# 608_AICarBoard_030102.net
KiCad netlist of a schematic drawn in EAGLE
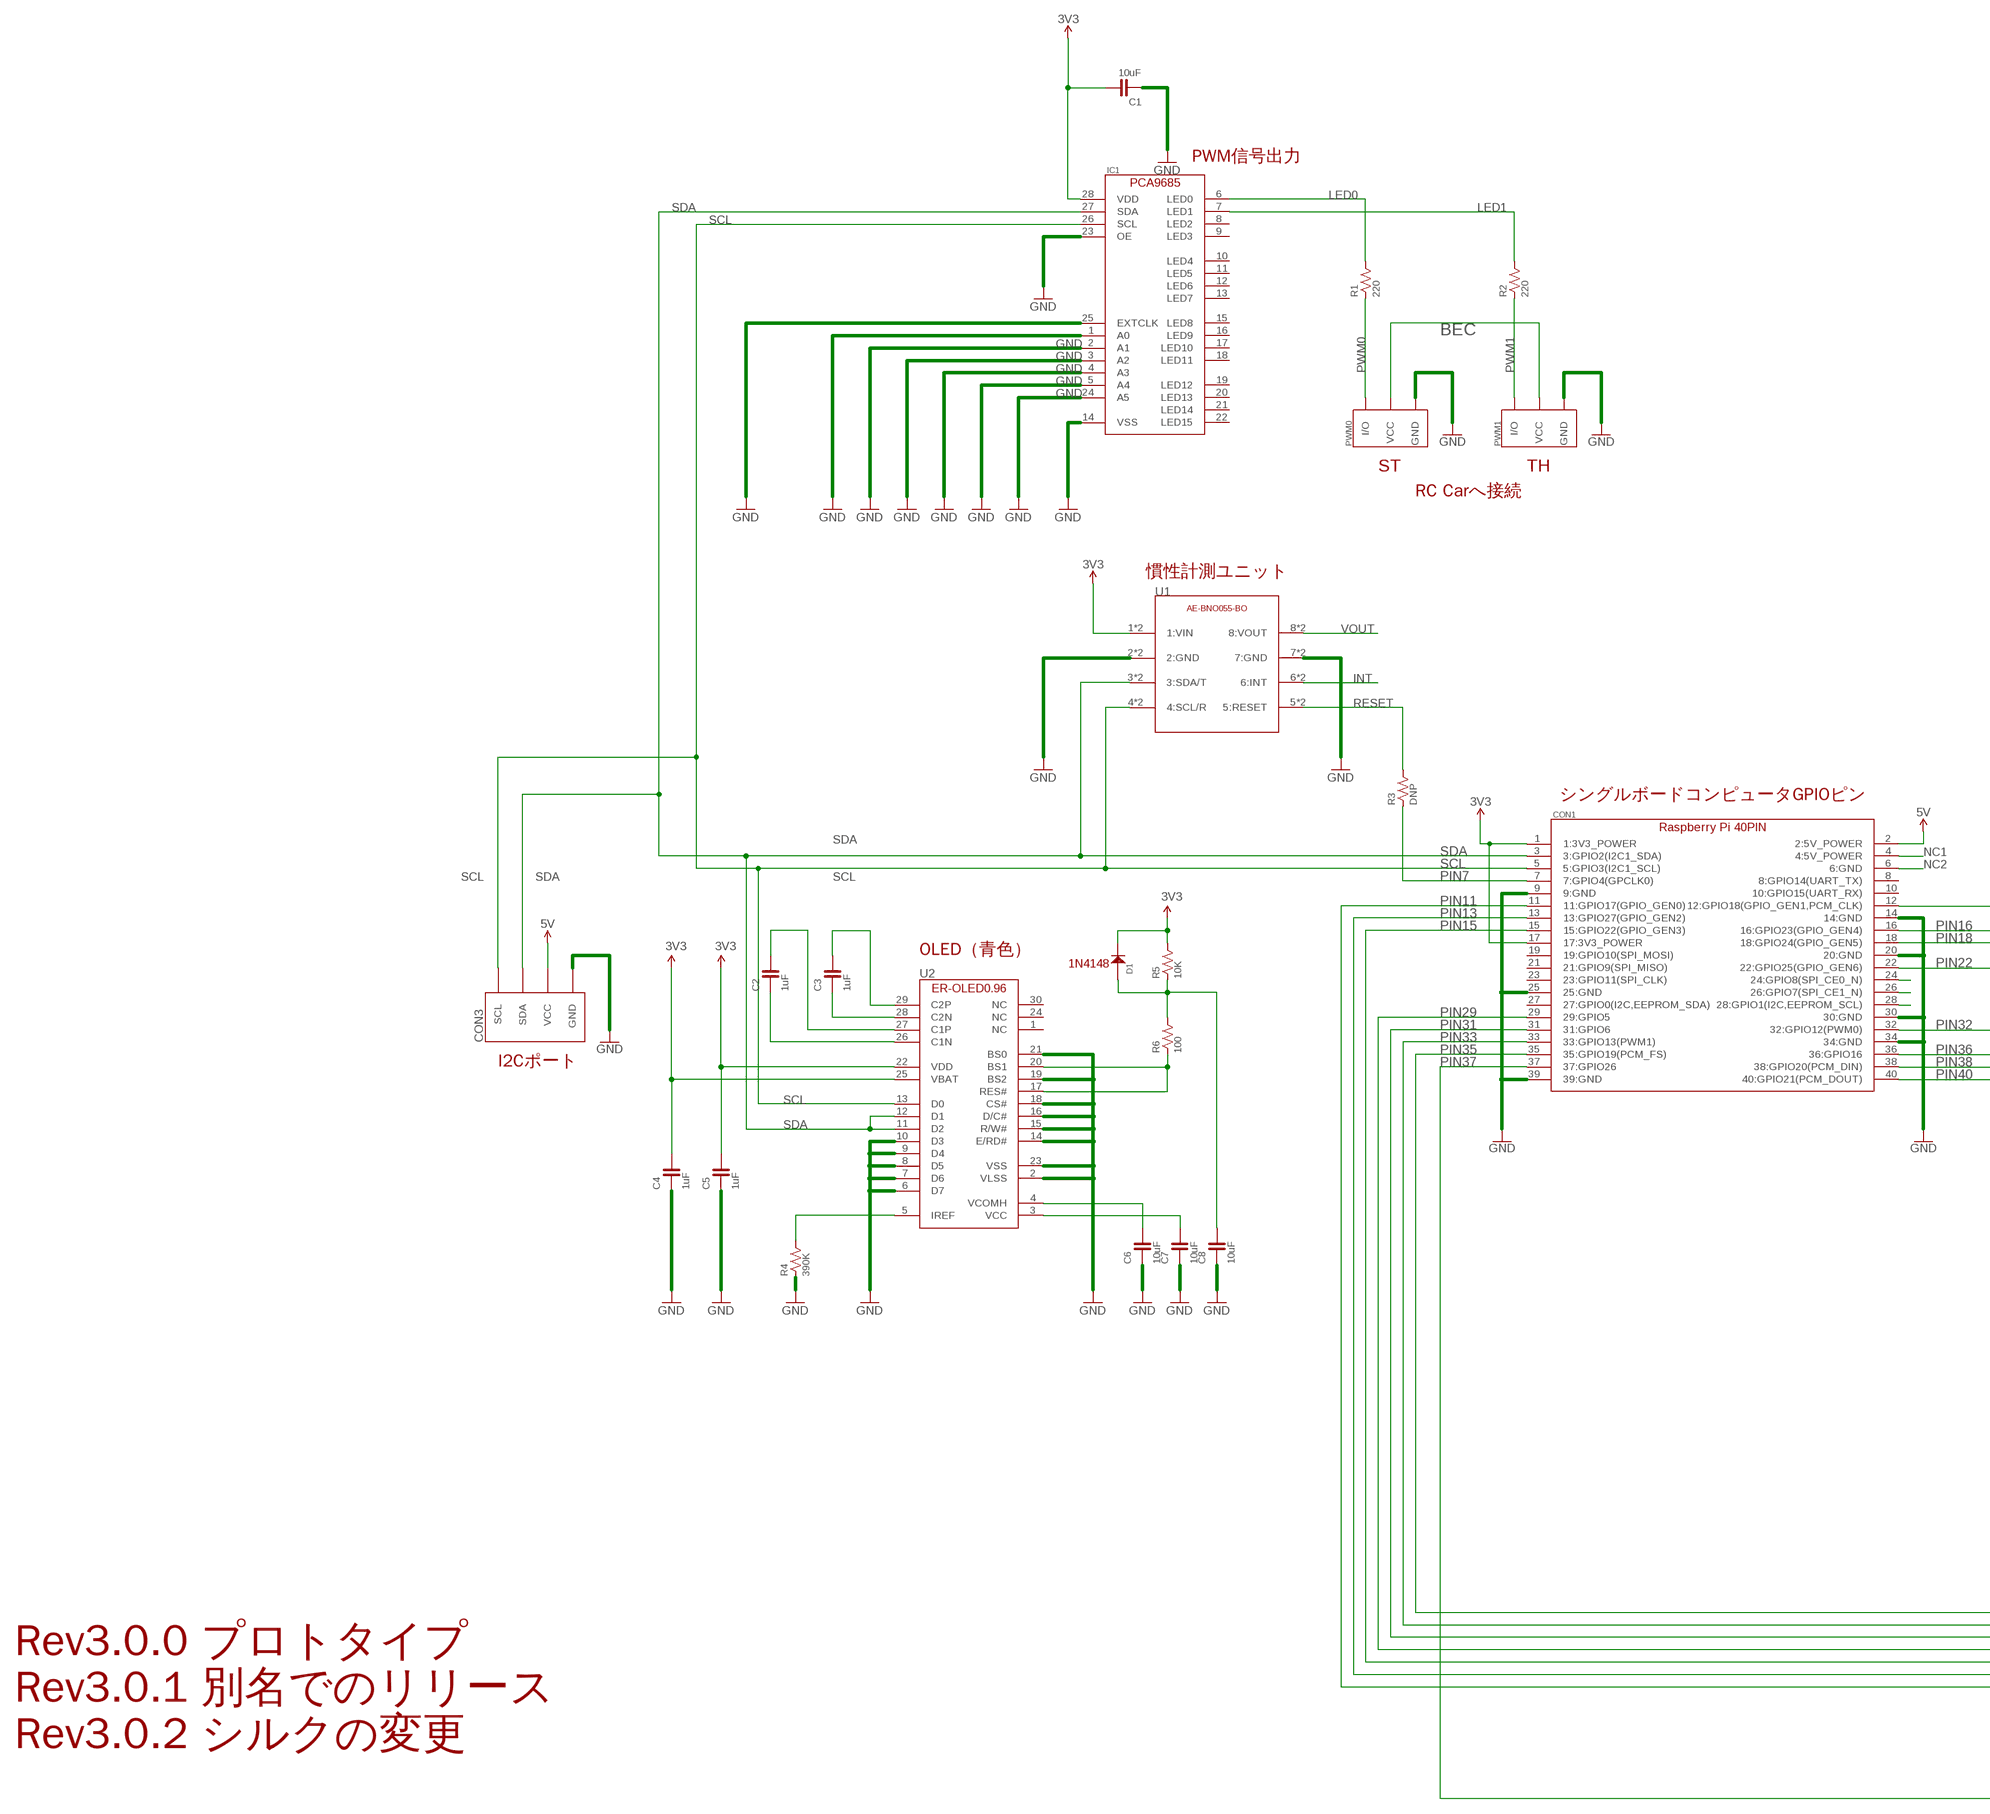
[diagram p0: schematic, sheet 1, part 1 of 3]
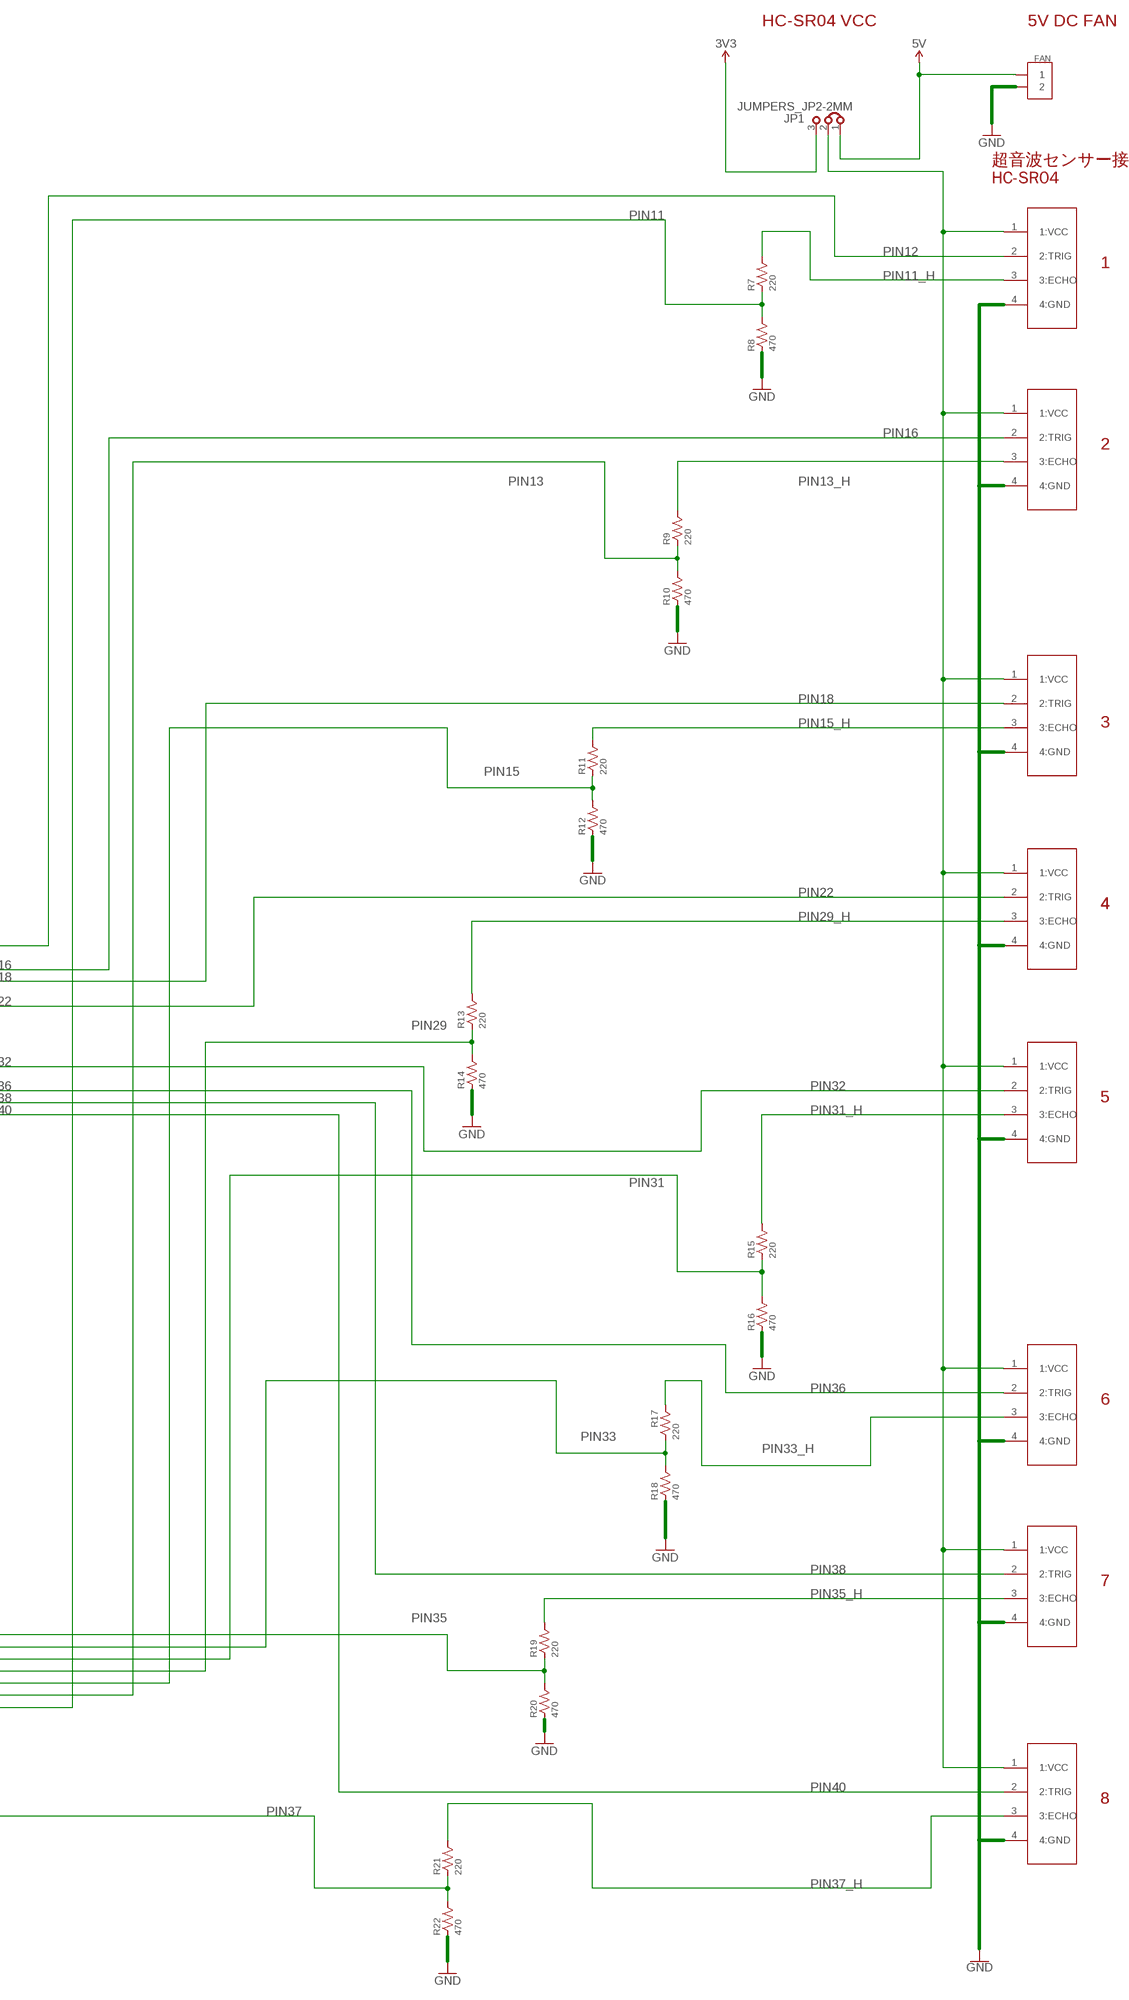
[diagram p1: schematic, sheet 1, part 2 of 3]
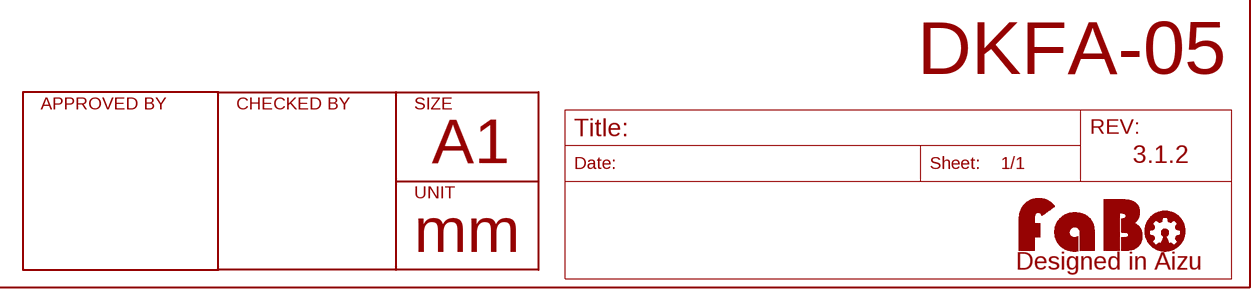
[diagram p2: schematic, sheet 1, part 3 of 3]

(export (version "E")
  (design (tool "Eeschema 10.0.6"))
  (components
    (comp (ref "C1")
      (value "10uF")
      (footprint "eagle-import:0603")
      (libsource (lib "eagle-import") (part "CAPACITOR-0603"))
    )
    (comp (ref "C2")
      (value "1uF")
      (footprint "eagle-import:0603-BOTTOM")
      (libsource (lib "eagle-import") (part "CAPACITOR-0603-BOTTOM"))
    )
    (comp (ref "C3")
      (value "1uF")
      (footprint "eagle-import:0603-BOTTOM")
      (libsource (lib "eagle-import") (part "CAPACITOR-0603-BOTTOM"))
    )
    (comp (ref "C4")
      (value "1uF")
      (footprint "eagle-import:0603-BOTTOM")
      (libsource (lib "eagle-import") (part "CAPACITOR-0603-BOTTOM"))
    )
    (comp (ref "C5")
      (value "1uF")
      (footprint "eagle-import:0603-BOTTOM")
      (libsource (lib "eagle-import") (part "CAPACITOR-0603-BOTTOM"))
    )
    (comp (ref "C6")
      (value "10uF")
      (footprint "eagle-import:0603-BOTTOM")
      (libsource (lib "eagle-import") (part "CAPACITOR-0603-BOTTOM"))
    )
    (comp (ref "C7")
      (value "10uF")
      (footprint "eagle-import:0603-BOTTOM")
      (libsource (lib "eagle-import") (part "CAPACITOR-0603-BOTTOM"))
    )
    (comp (ref "C8")
      (value "10uF")
      (footprint "eagle-import:0603-BOTTOM")
      (libsource (lib "eagle-import") (part "CAPACITOR-0603-BOTTOM"))
    )
    (comp (ref "CON1")
      (value "RASPBERRYPI_SHEILD")
      (footprint "eagle-import:RASPBERRY_PI_SHILED")
      (libsource (lib "eagle-import") (part "RASPBERRYPI_SHEILD"))
    )
    (comp (ref "CON3")
      (value "FABO_BRICK_I2C-S04B-PASK-2")
      (footprint "eagle-import:FABO_BRICK_I2C_S04B-PASK-2")
      (libsource (lib "eagle-import") (part "FABO_BRICK_I2C-S04B-PASK-2"))
    )
    (comp (ref "D1")
      (value "1N4148")
      (footprint "eagle-import:1N4148W")
      (libsource (lib "eagle-import") (part "1N4148"))
    )
    (comp (ref "FAN")
      (value "PIN_1X2")
      (footprint "eagle-import:PIN_1X2")
      (libsource (lib "eagle-import") (part "PIN_1X2"))
    )
    (comp (ref "HC1")
      (value "HC-SR04CONHS-SR04CON-SPEACING")
      (footprint "eagle-import:HC-SR04CON-SPEACE")
      (libsource (lib "eagle-import") (part "HC-SR04CONHS-SR04CON-SPEACING"))
    )
    (comp (ref "HC2")
      (value "HC-SR04CONHS-SR04CON-SPEACING")
      (footprint "eagle-import:HC-SR04CON-SPEACE")
      (libsource (lib "eagle-import") (part "HC-SR04CONHS-SR04CON-SPEACING"))
    )
    (comp (ref "HC3")
      (value "HC-SR04CONHS-SR04CON-SPEACING")
      (footprint "eagle-import:HC-SR04CON-SPEACE")
      (libsource (lib "eagle-import") (part "HC-SR04CONHS-SR04CON-SPEACING"))
    )
    (comp (ref "HC4")
      (value "HC-SR04CONHS-SR04CON-SPEACING")
      (footprint "eagle-import:HC-SR04CON-SPEACE")
      (libsource (lib "eagle-import") (part "HC-SR04CONHS-SR04CON-SPEACING"))
    )
    (comp (ref "HC5")
      (value "HC-SR04CONHS-SR04CON-SPEACING")
      (footprint "eagle-import:HC-SR04CON-SPEACE")
      (libsource (lib "eagle-import") (part "HC-SR04CONHS-SR04CON-SPEACING"))
    )
    (comp (ref "HC6")
      (value "HC-SR04CONHS-SR04CON-SPEACING")
      (footprint "eagle-import:HC-SR04CON-SPEACE")
      (libsource (lib "eagle-import") (part "HC-SR04CONHS-SR04CON-SPEACING"))
    )
    (comp (ref "HC7")
      (value "HC-SR04CONHS-SR04CON-SPEACING")
      (footprint "eagle-import:HC-SR04CON-SPEACE")
      (libsource (lib "eagle-import") (part "HC-SR04CONHS-SR04CON-SPEACING"))
    )
    (comp (ref "HC8")
      (value "HC-SR04CONHS-SR04CON-SPEACING")
      (footprint "eagle-import:HC-SR04CON-SPEACE")
      (libsource (lib "eagle-import") (part "HC-SR04CONHS-SR04CON-SPEACING"))
    )
    (comp (ref "IC1")
      (value "PCA9685BS")
      (footprint "eagle-import:PCA9685")
      (libsource (lib "eagle-import") (part "PCA9685BS"))
    )
    (comp (ref "JP1")
      (value "JUMPERS_JP2-2MM")
      (footprint "eagle-import:JUMPERS_JP2-2MM")
      (libsource (lib "eagle-import") (part "JUMPERS_JP2-2MM"))
    )
    (comp (ref "LOGO1")
      (value "LOGO_FABO-M")
      (footprint "eagle-import:LOGO_FABO_M")
      (libsource (lib "eagle-import") (part "LOGO_FABO-M"))
    )
    (comp (ref "PWM0")
      (value "PWM0")
      (footprint "eagle-import:PIN_1X3_NARROW")
      (libsource (lib "eagle-import") (part "FABO-BRICK-3PIN_HEADER"))
    )
    (comp (ref "PWM1")
      (value "PWM1")
      (footprint "eagle-import:PIN_1X3_NARROW")
      (libsource (lib "eagle-import") (part "FABO-BRICK-3PIN_HEADER"))
    )
    (comp (ref "R1")
      (value "220")
      (footprint "eagle-import:0603")
      (libsource (lib "eagle-import") (part "RESISTOR-0603"))
    )
    (comp (ref "R2")
      (value "220")
      (footprint "eagle-import:0603")
      (libsource (lib "eagle-import") (part "RESISTOR-0603"))
    )
    (comp (ref "R3")
      (value "DNP")
      (footprint "eagle-import:0603-BOTTOM")
      (libsource (lib "eagle-import") (part "RESISTOR-0603-BOTTOM"))
    )
    (comp (ref "R4")
      (value "390K")
      (footprint "eagle-import:0603-BOTTOM")
      (libsource (lib "eagle-import") (part "RESISTOR-0603-BOTTOM"))
    )
    (comp (ref "R5")
      (value "10K")
      (footprint "eagle-import:0603-BOTTOM")
      (libsource (lib "eagle-import") (part "RESISTOR-0603-BOTTOM"))
    )
    (comp (ref "R6")
      (value "100")
      (footprint "eagle-import:0603-BOTTOM")
      (libsource (lib "eagle-import") (part "RESISTOR-0603-BOTTOM"))
    )
    (comp (ref "R7")
      (value "220")
      (footprint "eagle-import:0603")
      (libsource (lib "eagle-import") (part "RESISTOR-0603"))
    )
    (comp (ref "R8")
      (value "470")
      (footprint "eagle-import:0603")
      (libsource (lib "eagle-import") (part "RESISTOR-0603"))
    )
    (comp (ref "R9")
      (value "220")
      (footprint "eagle-import:0603")
      (libsource (lib "eagle-import") (part "RESISTOR-0603"))
    )
    (comp (ref "R10")
      (value "470")
      (footprint "eagle-import:0603")
      (libsource (lib "eagle-import") (part "RESISTOR-0603"))
    )
    (comp (ref "R11")
      (value "220")
      (footprint "eagle-import:0603")
      (libsource (lib "eagle-import") (part "RESISTOR-0603"))
    )
    (comp (ref "R12")
      (value "470")
      (footprint "eagle-import:0603")
      (libsource (lib "eagle-import") (part "RESISTOR-0603"))
    )
    (comp (ref "R13")
      (value "220")
      (footprint "eagle-import:0603")
      (libsource (lib "eagle-import") (part "RESISTOR-0603"))
    )
    (comp (ref "R14")
      (value "470")
      (footprint "eagle-import:0603")
      (libsource (lib "eagle-import") (part "RESISTOR-0603"))
    )
    (comp (ref "R15")
      (value "220")
      (footprint "eagle-import:0603")
      (libsource (lib "eagle-import") (part "RESISTOR-0603"))
    )
    (comp (ref "R16")
      (value "470")
      (footprint "eagle-import:0603")
      (libsource (lib "eagle-import") (part "RESISTOR-0603"))
    )
    (comp (ref "R17")
      (value "220")
      (footprint "eagle-import:0603")
      (libsource (lib "eagle-import") (part "RESISTOR-0603"))
    )
    (comp (ref "R18")
      (value "470")
      (footprint "eagle-import:0603")
      (libsource (lib "eagle-import") (part "RESISTOR-0603"))
    )
    (comp (ref "R19")
      (value "220")
      (footprint "eagle-import:0603")
      (libsource (lib "eagle-import") (part "RESISTOR-0603"))
    )
    (comp (ref "R20")
      (value "470")
      (footprint "eagle-import:0603")
      (libsource (lib "eagle-import") (part "RESISTOR-0603"))
    )
    (comp (ref "R21")
      (value "220")
      (footprint "eagle-import:0603")
      (libsource (lib "eagle-import") (part "RESISTOR-0603"))
    )
    (comp (ref "R22")
      (value "470")
      (footprint "eagle-import:0603")
      (libsource (lib "eagle-import") (part "RESISTOR-0603"))
    )
    (comp (ref "U1")
      (value "AE-BNO055-BO")
      (footprint "eagle-import:DIP_8")
      (libsource (lib "eagle-import") (part "AE-BNO055-BO"))
    )
    (comp (ref "U2")
      (value "ER-OLED0.96-1ER-CON30HT-1_REV2")
      (footprint "eagle-import:ER-CON30HT-1_REV2")
      (libsource (lib "eagle-import") (part "ER-OLED0.96-1ER-CON30HT-1_REV2"))
    )
  )
  (nets
    (net (code "1") (name "/BEC") (class "Default")
      (node (ref "PWM0") (pin "2") (pinfunction "VCC_2") (pintype "bidirectional"))
      (node (ref "PWM1") (pin "2") (pinfunction "VCC_2") (pintype "bidirectional"))
    )
    (net (code "2") (name "/INT") (class "Default")
      (node (ref "U1") (pin "6") (pinfunction "6:INT_6") (pintype "output"))
      (node (ref "U1") (pin "6-1") (pinfunction "6:INT_6-1") (pintype "output"))
    )
    (net (code "3") (name "/LED0") (class "Default")
      (node (ref "IC1") (pin "6") (pinfunction "LED0_6") (pintype "bidirectional"))
      (node (ref "R1") (pin "2") (pinfunction "2_2") (pintype "bidirectional"))
    )
    (net (code "4") (name "/LED1") (class "Default")
      (node (ref "IC1") (pin "7") (pinfunction "LED1_7") (pintype "bidirectional"))
      (node (ref "R2") (pin "2") (pinfunction "2_2") (pintype "bidirectional"))
    )
    (net (code "5") (name "/NC1") (class "Default")
      (node (ref "CON1") (pin "4") (pinfunction "4:5V_POWER_4") (pintype "power_in"))
    )
    (net (code "6") (name "/NC2") (class "Default")
      (node (ref "CON1") (pin "6") (pinfunction "6:GND_6") (pintype "power_in"))
    )
    (net (code "7") (name "/PIN7") (class "Default")
      (node (ref "CON1") (pin "7") (pinfunction "7:GPIO4(GPCLK0)_7") (pintype "bidirectional"))
      (node (ref "R3") (pin "1") (pinfunction "1_1") (pintype "bidirectional"))
    )
    (net (code "8") (name "/PIN11") (class "Default")
      (node (ref "CON1") (pin "11") (pinfunction "11:GPIO17(GPIO_GEN0)_11") (pintype "bidirectional"))
      (node (ref "R7") (pin "1") (pinfunction "1_1") (pintype "bidirectional"))
      (node (ref "R8") (pin "2") (pinfunction "2_2") (pintype "bidirectional"))
    )
    (net (code "9") (name "/PIN11_H") (class "Default")
      (node (ref "HC1") (pin "3") (pinfunction "3:ECHO_3") (pintype "bidirectional"))
      (node (ref "R7") (pin "2") (pinfunction "2_2") (pintype "bidirectional"))
    )
    (net (code "10") (name "/PIN12") (class "Default")
      (node (ref "CON1") (pin "12") (pinfunction "12:GPIO18(GPIO_GEN1,PCM_CLK)_12") (pintype "bidirectional"))
      (node (ref "HC1") (pin "2") (pinfunction "2:TRIG_2") (pintype "bidirectional"))
    )
    (net (code "11") (name "/PIN13") (class "Default")
      (node (ref "CON1") (pin "13") (pinfunction "13:GPIO27(GPIO_GEN2)_13") (pintype "bidirectional"))
      (node (ref "R10") (pin "2") (pinfunction "2_2") (pintype "bidirectional"))
      (node (ref "R9") (pin "1") (pinfunction "1_1") (pintype "bidirectional"))
    )
    (net (code "12") (name "/PIN13_H") (class "Default")
      (node (ref "HC2") (pin "3") (pinfunction "3:ECHO_3") (pintype "bidirectional"))
      (node (ref "R9") (pin "2") (pinfunction "2_2") (pintype "bidirectional"))
    )
    (net (code "13") (name "/PIN15") (class "Default")
      (node (ref "CON1") (pin "15") (pinfunction "15:GPIO22(GPIO_GEN3)_15") (pintype "bidirectional"))
      (node (ref "R11") (pin "1") (pinfunction "1_1") (pintype "bidirectional"))
      (node (ref "R12") (pin "2") (pinfunction "2_2") (pintype "bidirectional"))
    )
    (net (code "14") (name "/PIN15_H") (class "Default")
      (node (ref "HC3") (pin "3") (pinfunction "3:ECHO_3") (pintype "bidirectional"))
      (node (ref "R11") (pin "2") (pinfunction "2_2") (pintype "bidirectional"))
    )
    (net (code "15") (name "/PIN16") (class "Default")
      (node (ref "CON1") (pin "16") (pinfunction "16:GPIO23(GPIO_GEN4)_16") (pintype "bidirectional"))
      (node (ref "HC2") (pin "2") (pinfunction "2:TRIG_2") (pintype "bidirectional"))
    )
    (net (code "16") (name "/PIN18") (class "Default")
      (node (ref "CON1") (pin "18") (pinfunction "18:GPIO24(GPIO_GEN5)_18") (pintype "bidirectional"))
      (node (ref "HC3") (pin "2") (pinfunction "2:TRIG_2") (pintype "bidirectional"))
    )
    (net (code "17") (name "/PIN22") (class "Default")
      (node (ref "CON1") (pin "22") (pinfunction "22:GPIO25(GPIO_GEN6)_22") (pintype "bidirectional"))
      (node (ref "HC4") (pin "2") (pinfunction "2:TRIG_2") (pintype "bidirectional"))
    )
    (net (code "18") (name "/PIN29") (class "Default")
      (node (ref "CON1") (pin "29") (pinfunction "29:GPIO5_29") (pintype "bidirectional"))
      (node (ref "R13") (pin "1") (pinfunction "1_1") (pintype "bidirectional"))
      (node (ref "R14") (pin "2") (pinfunction "2_2") (pintype "bidirectional"))
    )
    (net (code "19") (name "/PIN29_H") (class "Default")
      (node (ref "HC4") (pin "3") (pinfunction "3:ECHO_3") (pintype "bidirectional"))
      (node (ref "R13") (pin "2") (pinfunction "2_2") (pintype "bidirectional"))
    )
    (net (code "20") (name "/PIN31") (class "Default")
      (node (ref "CON1") (pin "31") (pinfunction "31:GPIO6_31") (pintype "bidirectional"))
      (node (ref "R15") (pin "1") (pinfunction "1_1") (pintype "bidirectional"))
      (node (ref "R16") (pin "2") (pinfunction "2_2") (pintype "bidirectional"))
    )
    (net (code "21") (name "/PIN31_H") (class "Default")
      (node (ref "HC5") (pin "3") (pinfunction "3:ECHO_3") (pintype "bidirectional"))
      (node (ref "R15") (pin "2") (pinfunction "2_2") (pintype "bidirectional"))
    )
    (net (code "22") (name "/PIN32") (class "Default")
      (node (ref "CON1") (pin "32") (pinfunction "32:GPIO12(PWM0)_32") (pintype "bidirectional"))
      (node (ref "HC5") (pin "2") (pinfunction "2:TRIG_2") (pintype "bidirectional"))
    )
    (net (code "23") (name "/PIN33") (class "Default")
      (node (ref "CON1") (pin "33") (pinfunction "33:GPIO13(PWM1)_33") (pintype "bidirectional"))
      (node (ref "R17") (pin "1") (pinfunction "1_1") (pintype "bidirectional"))
      (node (ref "R18") (pin "2") (pinfunction "2_2") (pintype "bidirectional"))
    )
    (net (code "24") (name "/PIN33_H") (class "Default")
      (node (ref "HC6") (pin "3") (pinfunction "3:ECHO_3") (pintype "bidirectional"))
      (node (ref "R17") (pin "2") (pinfunction "2_2") (pintype "bidirectional"))
    )
    (net (code "25") (name "/PIN35") (class "Default")
      (node (ref "CON1") (pin "35") (pinfunction "35:GPIO19(PCM_FS)_35") (pintype "bidirectional"))
      (node (ref "R19") (pin "1") (pinfunction "1_1") (pintype "bidirectional"))
      (node (ref "R20") (pin "2") (pinfunction "2_2") (pintype "bidirectional"))
    )
    (net (code "26") (name "/PIN35_H") (class "Default")
      (node (ref "HC7") (pin "3") (pinfunction "3:ECHO_3") (pintype "bidirectional"))
      (node (ref "R19") (pin "2") (pinfunction "2_2") (pintype "bidirectional"))
    )
    (net (code "27") (name "/PIN36") (class "Default")
      (node (ref "CON1") (pin "36") (pinfunction "36:GPIO16_36") (pintype "bidirectional"))
      (node (ref "HC6") (pin "2") (pinfunction "2:TRIG_2") (pintype "bidirectional"))
    )
    (net (code "28") (name "/PIN37") (class "Default")
      (node (ref "CON1") (pin "37") (pinfunction "37:GPIO26_37") (pintype "bidirectional"))
      (node (ref "R21") (pin "1") (pinfunction "1_1") (pintype "bidirectional"))
      (node (ref "R22") (pin "2") (pinfunction "2_2") (pintype "bidirectional"))
    )
    (net (code "29") (name "/PIN37_H") (class "Default")
      (node (ref "HC8") (pin "3") (pinfunction "3:ECHO_3") (pintype "bidirectional"))
      (node (ref "R21") (pin "2") (pinfunction "2_2") (pintype "bidirectional"))
    )
    (net (code "30") (name "/PIN38") (class "Default")
      (node (ref "CON1") (pin "38") (pinfunction "38:GPIO20(PCM_DIN)_38") (pintype "bidirectional"))
      (node (ref "HC7") (pin "2") (pinfunction "2:TRIG_2") (pintype "bidirectional"))
    )
    (net (code "31") (name "/PIN40") (class "Default")
      (node (ref "CON1") (pin "40") (pinfunction "40:GPIO21(PCM_DOUT)_40") (pintype "bidirectional"))
      (node (ref "HC8") (pin "2") (pinfunction "2:TRIG_2") (pintype "bidirectional"))
    )
    (net (code "32") (name "/PWM0") (class "Default")
      (node (ref "PWM0") (pin "1") (pinfunction "I/O_1") (pintype "bidirectional"))
      (node (ref "R1") (pin "1") (pinfunction "1_1") (pintype "bidirectional"))
    )
    (net (code "33") (name "/PWM1") (class "Default")
      (node (ref "PWM1") (pin "1") (pinfunction "I/O_1") (pintype "bidirectional"))
      (node (ref "R2") (pin "1") (pinfunction "1_1") (pintype "bidirectional"))
    )
    (net (code "34") (name "/RESET") (class "Default")
      (node (ref "R3") (pin "2") (pinfunction "2_2") (pintype "bidirectional"))
      (node (ref "U1") (pin "5") (pinfunction "5:RESET_5") (pintype "input"))
      (node (ref "U1") (pin "5-1") (pinfunction "5:RESET_5-1") (pintype "input"))
    )
    (net (code "35") (name "/SCL") (class "Default")
      (node (ref "CON1") (pin "5") (pinfunction "5:GPIO3(I2C1_SCL)_5") (pintype "bidirectional"))
      (node (ref "CON3") (pin "SCL") (pinfunction "SCL_SCL") (pintype "bidirectional"))
      (node (ref "IC1") (pin "26") (pinfunction "SCL_26") (pintype "bidirectional"))
      (node (ref "U1") (pin "4") (pinfunction "4:SCL/R_4") (pintype "bidirectional"))
      (node (ref "U1") (pin "4-1") (pinfunction "4:SCL/R_4-1") (pintype "bidirectional"))
      (node (ref "U2") (pin "13") (pinfunction "D0_13") (pintype "bidirectional"))
    )
    (net (code "36") (name "/SDA") (class "Default")
      (node (ref "CON1") (pin "3") (pinfunction "3:GPIO2(I2C1_SDA)_3") (pintype "bidirectional"))
      (node (ref "CON3") (pin "SDA") (pinfunction "SDA_SDA") (pintype "bidirectional"))
      (node (ref "IC1") (pin "27") (pinfunction "SDA_27") (pintype "bidirectional"))
      (node (ref "U1") (pin "3") (pinfunction "3:SDA/T_3") (pintype "bidirectional"))
      (node (ref "U1") (pin "3-1") (pinfunction "3:SDA/T_3-1") (pintype "bidirectional"))
      (node (ref "U2") (pin "11") (pinfunction "D2_11") (pintype "bidirectional"))
      (node (ref "U2") (pin "12") (pinfunction "D1_12") (pintype "bidirectional"))
    )
    (net (code "37") (name "/VOUT") (class "Default")
      (node (ref "U1") (pin "8") (pinfunction "8:VOUT_8") (pintype "power_in"))
      (node (ref "U1") (pin "8-1") (pinfunction "8:VOUT_8-1") (pintype "power_in"))
    )
    (net (code "38") (name "3V3") (class "Default")
      (node (ref "C1") (pin "2") (pinfunction "2_2") (pintype "passive"))
      (node (ref "C4") (pin "2") (pinfunction "2_2") (pintype "passive"))
      (node (ref "C5") (pin "2") (pinfunction "2_2") (pintype "passive"))
      (node (ref "CON1") (pin "1") (pinfunction "1:3V3_POWER_1") (pintype "power_in"))
      (node (ref "CON1") (pin "17") (pinfunction "17:3V3_POWER_17") (pintype "power_in"))
      (node (ref "D1") (pin "CATHODE") (pinfunction "CATHODE_CATHODE") (pintype "bidirectional"))
      (node (ref "IC1") (pin "28") (pinfunction "VDD_28") (pintype "bidirectional"))
      (node (ref "JP1") (pin "3") (pinfunction "3_3") (pintype "passive"))
      (node (ref "R5") (pin "2") (pinfunction "2_2") (pintype "bidirectional"))
      (node (ref "U1") (pin "1") (pinfunction "1:VIN_1") (pintype "power_in"))
      (node (ref "U1") (pin "1-1") (pinfunction "1:VIN_1-1") (pintype "power_in"))
      (node (ref "U2") (pin "22") (pinfunction "VDD_22") (pintype "bidirectional"))
      (node (ref "U2") (pin "25") (pinfunction "VBAT_25") (pintype "bidirectional"))
    )
    (net (code "39") (name "5V") (class "Default")
      (node (ref "CON1") (pin "2") (pinfunction "2:5V_POWER_2") (pintype "power_in"))
      (node (ref "CON3") (pin "VCC") (pinfunction "VCC_VCC") (pintype "bidirectional"))
      (node (ref "FAN") (pin "1") (pinfunction "1_1") (pintype "bidirectional"))
      (node (ref "JP1") (pin "1") (pinfunction "1_1") (pintype "passive"))
    )
    (net (code "40") (name "GND") (class "Default")
      (node (ref "C1") (pin "1") (pinfunction "1_1") (pintype "passive"))
      (node (ref "C4") (pin "1") (pinfunction "1_1") (pintype "passive"))
      (node (ref "C5") (pin "1") (pinfunction "1_1") (pintype "passive"))
      (node (ref "C6") (pin "1") (pinfunction "1_1") (pintype "passive"))
      (node (ref "C7") (pin "1") (pinfunction "1_1") (pintype "passive"))
      (node (ref "C8") (pin "1") (pinfunction "1_1") (pintype "passive"))
      (node (ref "CON1") (pin "14") (pinfunction "14:GND_14") (pintype "power_in"))
      (node (ref "CON1") (pin "20") (pinfunction "20:GND_20") (pintype "power_in"))
      (node (ref "CON1") (pin "25") (pinfunction "25:GND_25") (pintype "power_in"))
      (node (ref "CON1") (pin "30") (pinfunction "30:GND_30") (pintype "power_in"))
      (node (ref "CON1") (pin "34") (pinfunction "34:GND_34") (pintype "power_in"))
      (node (ref "CON1") (pin "39") (pinfunction "39:GND_39") (pintype "power_in"))
      (node (ref "CON1") (pin "9") (pinfunction "9:GND_9") (pintype "power_in"))
      (node (ref "CON3") (pin "GND") (pinfunction "GND_GND") (pintype "bidirectional"))
      (node (ref "FAN") (pin "2") (pinfunction "2_2") (pintype "bidirectional"))
      (node (ref "HC1") (pin "4") (pinfunction "4:GND_4") (pintype "bidirectional"))
      (node (ref "HC2") (pin "4") (pinfunction "4:GND_4") (pintype "bidirectional"))
      (node (ref "HC3") (pin "4") (pinfunction "4:GND_4") (pintype "bidirectional"))
      (node (ref "HC4") (pin "4") (pinfunction "4:GND_4") (pintype "bidirectional"))
      (node (ref "HC5") (pin "4") (pinfunction "4:GND_4") (pintype "bidirectional"))
      (node (ref "HC6") (pin "4") (pinfunction "4:GND_4") (pintype "bidirectional"))
      (node (ref "HC7") (pin "4") (pinfunction "4:GND_4") (pintype "bidirectional"))
      (node (ref "HC8") (pin "4") (pinfunction "4:GND_4") (pintype "bidirectional"))
      (node (ref "IC1") (pin "1") (pinfunction "A0_1") (pintype "bidirectional"))
      (node (ref "IC1") (pin "14") (pinfunction "VSS_14") (pintype "bidirectional"))
      (node (ref "IC1") (pin "2") (pinfunction "A1_2") (pintype "bidirectional"))
      (node (ref "IC1") (pin "23") (pinfunction "OE_23") (pintype "bidirectional"))
      (node (ref "IC1") (pin "24") (pinfunction "A5_24") (pintype "bidirectional"))
      (node (ref "IC1") (pin "25") (pinfunction "EXTCLK_25") (pintype "bidirectional"))
      (node (ref "IC1") (pin "3") (pinfunction "A2_3") (pintype "bidirectional"))
      (node (ref "IC1") (pin "4") (pinfunction "A3_4") (pintype "bidirectional"))
      (node (ref "IC1") (pin "5") (pinfunction "A4_5") (pintype "bidirectional"))
      (node (ref "PWM0") (pin "3") (pinfunction "GND_3") (pintype "bidirectional"))
      (node (ref "PWM1") (pin "3") (pinfunction "GND_3") (pintype "bidirectional"))
      (node (ref "R10") (pin "1") (pinfunction "1_1") (pintype "bidirectional"))
      (node (ref "R12") (pin "1") (pinfunction "1_1") (pintype "bidirectional"))
      (node (ref "R14") (pin "1") (pinfunction "1_1") (pintype "bidirectional"))
      (node (ref "R16") (pin "1") (pinfunction "1_1") (pintype "bidirectional"))
      (node (ref "R18") (pin "1") (pinfunction "1_1") (pintype "bidirectional"))
      (node (ref "R20") (pin "1") (pinfunction "1_1") (pintype "bidirectional"))
      (node (ref "R22") (pin "1") (pinfunction "1_1") (pintype "bidirectional"))
      (node (ref "R4") (pin "1") (pinfunction "1_1") (pintype "bidirectional"))
      (node (ref "R8") (pin "1") (pinfunction "1_1") (pintype "bidirectional"))
      (node (ref "U1") (pin "2") (pinfunction "2:GND_2") (pintype "power_in"))
      (node (ref "U1") (pin "2-1") (pinfunction "2:GND_2-1") (pintype "power_in"))
      (node (ref "U1") (pin "7") (pinfunction "7:GND_7") (pintype "power_in"))
      (node (ref "U1") (pin "7-1") (pinfunction "7:GND_7-1") (pintype "power_in"))
      (node (ref "U2") (pin "10") (pinfunction "D3_10") (pintype "bidirectional"))
      (node (ref "U2") (pin "14") (pinfunction "E/RD#_14") (pintype "bidirectional"))
      (node (ref "U2") (pin "15") (pinfunction "R/W#_15") (pintype "bidirectional"))
      (node (ref "U2") (pin "16") (pinfunction "D/C#_16") (pintype "bidirectional"))
      (node (ref "U2") (pin "18") (pinfunction "CS#_18") (pintype "bidirectional"))
      (node (ref "U2") (pin "19") (pinfunction "BS2_19") (pintype "bidirectional"))
      (node (ref "U2") (pin "2") (pinfunction "VLSS_2") (pintype "bidirectional"))
      (node (ref "U2") (pin "21") (pinfunction "BS0_21") (pintype "bidirectional"))
      (node (ref "U2") (pin "23") (pinfunction "VSS_23") (pintype "bidirectional"))
      (node (ref "U2") (pin "6") (pinfunction "D7_6") (pintype "bidirectional"))
      (node (ref "U2") (pin "7") (pinfunction "D6_7") (pintype "bidirectional"))
      (node (ref "U2") (pin "8") (pinfunction "D5_8") (pintype "bidirectional"))
      (node (ref "U2") (pin "9") (pinfunction "D4_9") (pintype "bidirectional"))
    )
    (net (code "41") (name "Net-(C8-Pad2)") (class "Default")
      (node (ref "C8") (pin "2") (pinfunction "2_2") (pintype "passive"))
      (node (ref "D1") (pin "ANODE") (pinfunction "ANODE_ANODE") (pintype "bidirectional"))
      (node (ref "R5") (pin "1") (pinfunction "1_1") (pintype "bidirectional"))
      (node (ref "R6") (pin "2") (pinfunction "2_2") (pintype "bidirectional"))
    )
    (net (code "42") (name "Net-(HC1-1:VCC)") (class "Default")
      (node (ref "HC1") (pin "1") (pinfunction "1:VCC_1") (pintype "bidirectional"))
      (node (ref "HC2") (pin "1") (pinfunction "1:VCC_1") (pintype "bidirectional"))
      (node (ref "HC3") (pin "1") (pinfunction "1:VCC_1") (pintype "bidirectional"))
      (node (ref "HC4") (pin "1") (pinfunction "1:VCC_1") (pintype "bidirectional"))
      (node (ref "HC5") (pin "1") (pinfunction "1:VCC_1") (pintype "bidirectional"))
      (node (ref "HC6") (pin "1") (pinfunction "1:VCC_1") (pintype "bidirectional"))
      (node (ref "HC7") (pin "1") (pinfunction "1:VCC_1") (pintype "bidirectional"))
      (node (ref "HC8") (pin "1") (pinfunction "1:VCC_1") (pintype "bidirectional"))
      (node (ref "JP1") (pin "2") (pinfunction "2_2") (pintype "passive"))
    )
    (net (code "43") (name "Net-(U2-BS1)") (class "Default")
      (node (ref "R6") (pin "1") (pinfunction "1_1") (pintype "bidirectional"))
      (node (ref "U2") (pin "17") (pinfunction "RES#_17") (pintype "bidirectional"))
      (node (ref "U2") (pin "20") (pinfunction "BS1_20") (pintype "bidirectional"))
    )
    (net (code "44") (name "Net-(U2-C1N)") (class "Default")
      (node (ref "C2") (pin "1") (pinfunction "1_1") (pintype "passive"))
      (node (ref "U2") (pin "26") (pinfunction "C1N_26") (pintype "bidirectional"))
    )
    (net (code "45") (name "Net-(U2-C1P)") (class "Default")
      (node (ref "C2") (pin "2") (pinfunction "2_2") (pintype "passive"))
      (node (ref "U2") (pin "27") (pinfunction "C1P_27") (pintype "bidirectional"))
    )
    (net (code "46") (name "Net-(U2-C2N)") (class "Default")
      (node (ref "C3") (pin "1") (pinfunction "1_1") (pintype "passive"))
      (node (ref "U2") (pin "28") (pinfunction "C2N_28") (pintype "bidirectional"))
    )
    (net (code "47") (name "Net-(U2-C2P)") (class "Default")
      (node (ref "C3") (pin "2") (pinfunction "2_2") (pintype "passive"))
      (node (ref "U2") (pin "29") (pinfunction "C2P_29") (pintype "bidirectional"))
    )
    (net (code "48") (name "Net-(U2-IREF)") (class "Default")
      (node (ref "R4") (pin "2") (pinfunction "2_2") (pintype "bidirectional"))
      (node (ref "U2") (pin "5") (pinfunction "IREF_5") (pintype "bidirectional"))
    )
    (net (code "49") (name "Net-(U2-VCC)") (class "Default")
      (node (ref "C7") (pin "2") (pinfunction "2_2") (pintype "passive"))
      (node (ref "U2") (pin "3") (pinfunction "VCC_3") (pintype "bidirectional"))
    )
    (net (code "50") (name "Net-(U2-VCOMH)") (class "Default")
      (node (ref "C6") (pin "2") (pinfunction "2_2") (pintype "passive"))
      (node (ref "U2") (pin "4") (pinfunction "VCOMH_4") (pintype "bidirectional"))
    )
    (net (code "51") (name "unconnected-(CON1-8:GPIO14(UART_TX)-Pad8)") (class "Default")
      (node (ref "CON1") (pin "8") (pinfunction "8:GPIO14(UART_TX)_8") (pintype "bidirectional"))
    )
    (net (code "52") (name "unconnected-(CON1-10:GPIO15(UART_RX)-Pad10)") (class "Default")
      (node (ref "CON1") (pin "10") (pinfunction "10:GPIO15(UART_RX)_10") (pintype "bidirectional"))
    )
    (net (code "53") (name "unconnected-(CON1-19:GPIO10(SPI_MOSI)-Pad19)") (class "Default")
      (node (ref "CON1") (pin "19") (pinfunction "19:GPIO10(SPI_MOSI)_19") (pintype "bidirectional"))
    )
    (net (code "54") (name "unconnected-(CON1-21:GPIO9(SPI_MISO)-Pad21)") (class "Default")
      (node (ref "CON1") (pin "21") (pinfunction "21:GPIO9(SPI_MISO)_21") (pintype "bidirectional"))
    )
    (net (code "55") (name "unconnected-(CON1-23:GPIO11(SPI_CLK)-Pad23)") (class "Default")
      (node (ref "CON1") (pin "23") (pinfunction "23:GPIO11(SPI_CLK)_23") (pintype "bidirectional"))
    )
    (net (code "56") (name "unconnected-(CON1-24:GPIO8(SPI_CE0_N)-Pad24)") (class "Default")
      (node (ref "CON1") (pin "24") (pinfunction "24:GPIO8(SPI_CE0_N)_24") (pintype "bidirectional"))
    )
    (net (code "57") (name "unconnected-(CON1-26:GPIO7(SPI_CE1_N)-Pad26)") (class "Default")
      (node (ref "CON1") (pin "26") (pinfunction "26:GPIO7(SPI_CE1_N)_26") (pintype "bidirectional"))
    )
    (net (code "58") (name "unconnected-(CON1-27:GPIO0(I2C,EEPROM_SDA)-Pad27)") (class "Default")
      (node (ref "CON1") (pin "27") (pinfunction "27:GPIO0(I2C,EEPROM_SDA)_27") (pintype "bidirectional"))
    )
    (net (code "59") (name "unconnected-(CON1-28:GPIO1(I2C,EEPROM_SCL)-Pad28)") (class "Default")
      (node (ref "CON1") (pin "28") (pinfunction "28:GPIO1(I2C,EEPROM_SCL)_28") (pintype "bidirectional"))
    )
    (net (code "60") (name "unconnected-(IC1-LED2-Pad8)") (class "Default")
      (node (ref "IC1") (pin "8") (pinfunction "LED2_8") (pintype "bidirectional"))
    )
    (net (code "61") (name "unconnected-(IC1-LED3-Pad9)") (class "Default")
      (node (ref "IC1") (pin "9") (pinfunction "LED3_9") (pintype "bidirectional"))
    )
    (net (code "62") (name "unconnected-(IC1-LED4-Pad10)") (class "Default")
      (node (ref "IC1") (pin "10") (pinfunction "LED4_10") (pintype "bidirectional"))
    )
    (net (code "63") (name "unconnected-(IC1-LED5-Pad11)") (class "Default")
      (node (ref "IC1") (pin "11") (pinfunction "LED5_11") (pintype "bidirectional"))
    )
    (net (code "64") (name "unconnected-(IC1-LED6-Pad12)") (class "Default")
      (node (ref "IC1") (pin "12") (pinfunction "LED6_12") (pintype "bidirectional"))
    )
    (net (code "65") (name "unconnected-(IC1-LED7-Pad13)") (class "Default")
      (node (ref "IC1") (pin "13") (pinfunction "LED7_13") (pintype "bidirectional"))
    )
    (net (code "66") (name "unconnected-(IC1-LED8-Pad15)") (class "Default")
      (node (ref "IC1") (pin "15") (pinfunction "LED8_15") (pintype "bidirectional"))
    )
    (net (code "67") (name "unconnected-(IC1-LED9-Pad16)") (class "Default")
      (node (ref "IC1") (pin "16") (pinfunction "LED9_16") (pintype "bidirectional"))
    )
    (net (code "68") (name "unconnected-(IC1-LED10-Pad17)") (class "Default")
      (node (ref "IC1") (pin "17") (pinfunction "LED10_17") (pintype "bidirectional"))
    )
    (net (code "69") (name "unconnected-(IC1-LED11-Pad18)") (class "Default")
      (node (ref "IC1") (pin "18") (pinfunction "LED11_18") (pintype "bidirectional"))
    )
    (net (code "70") (name "unconnected-(IC1-LED12-Pad19)") (class "Default")
      (node (ref "IC1") (pin "19") (pinfunction "LED12_19") (pintype "bidirectional"))
    )
    (net (code "71") (name "unconnected-(IC1-LED13-Pad20)") (class "Default")
      (node (ref "IC1") (pin "20") (pinfunction "LED13_20") (pintype "bidirectional"))
    )
    (net (code "72") (name "unconnected-(IC1-LED14-Pad21)") (class "Default")
      (node (ref "IC1") (pin "21") (pinfunction "LED14_21") (pintype "bidirectional"))
    )
    (net (code "73") (name "unconnected-(IC1-LED15-Pad22)") (class "Default")
      (node (ref "IC1") (pin "22") (pinfunction "LED15_22") (pintype "bidirectional"))
    )
    (net (code "74") (name "unconnected-(U2-NC-Pad1)") (class "Default")
      (node (ref "U2") (pin "1") (pinfunction "NC_1") (pintype "bidirectional"))
    )
    (net (code "75") (name "unconnected-(U2-NC-Pad24)") (class "Default")
      (node (ref "U2") (pin "24") (pinfunction "NC_24") (pintype "bidirectional"))
    )
    (net (code "76") (name "unconnected-(U2-NC-Pad30)") (class "Default")
      (node (ref "U2") (pin "30") (pinfunction "NC_30") (pintype "bidirectional"))
    )
  )
)
